# sdcard.net
KiCad netlist of a schematic drawn in Altium Designer
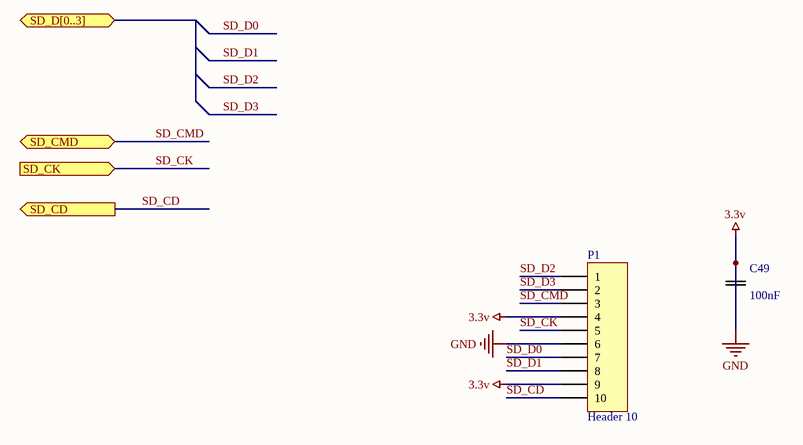
[diagram p0: sdcard.SchDoc]

(export (version "E")
  (design (tool "Eeschema 10.0.6"))
  (components
    (comp (ref "C49")
      (value "100nF")
      (footprint "CAPC2013X110N")
      (description "Capacitor; Ceramic; Cap; .100UF ; Tol+-10%; SMD; Vol-Rtg 50V; X7R, Tape/Reel")
      (fields (field (name "MP") "C0805C104K5RACTU") (field (name "MF") "Kemet"))
      (libsource (lib "100nF-C0805C104K5RACTU") (part "C0805C104K5RACTU"))
    )
    (comp (ref "P1")
      (value "Header 10")
      (footprint "HDR1X10")
      (description "Header, 10-Pin")
      (fields (field (name "PUBLISHER") "Altium Limited"))
      (libsource (lib "Miscellaneous Connectors") (part "Header 10"))
    )
  )
  (nets
    (net (code "1") (name "/SD_CD") (class "Default")
      (node (ref "P1") (pin "10") (pinfunction "10_10") (pintype "passive"))
    )
    (net (code "2") (name "/SD_CK") (class "Default")
      (node (ref "P1") (pin "5") (pinfunction "5_5") (pintype "passive"))
    )
    (net (code "3") (name "/SD_CMD") (class "Default")
      (node (ref "P1") (pin "3") (pinfunction "3_3") (pintype "passive"))
    )
    (net (code "4") (name "/SD_D0") (class "Default")
      (node (ref "P1") (pin "7") (pinfunction "7_7") (pintype "passive"))
    )
    (net (code "5") (name "/SD_D1") (class "Default")
      (node (ref "P1") (pin "8") (pinfunction "8_8") (pintype "passive"))
    )
    (net (code "6") (name "/SD_D2") (class "Default")
      (node (ref "P1") (pin "1") (pinfunction "1_1") (pintype "passive"))
    )
    (net (code "7") (name "/SD_D3") (class "Default")
      (node (ref "P1") (pin "2") (pinfunction "2_2") (pintype "passive"))
    )
    (net (code "9") (name "3.3v") (class "Default")
      (node (ref "C49") (pin "1") (pinfunction "C1_1") (pintype "passive"))
      (node (ref "C49") (pin "2") (pinfunction "C2_2") (pintype "passive"))
      (node (ref "P1") (pin "4") (pinfunction "4_4") (pintype "passive"))
      (node (ref "P1") (pin "6") (pinfunction "6_6") (pintype "passive"))
      (node (ref "P1") (pin "9") (pinfunction "9_9") (pintype "passive"))
    )
  )
)
